# rifting_bronx_eden.net
KiCad netlist of a schematic drawn in EAGLE
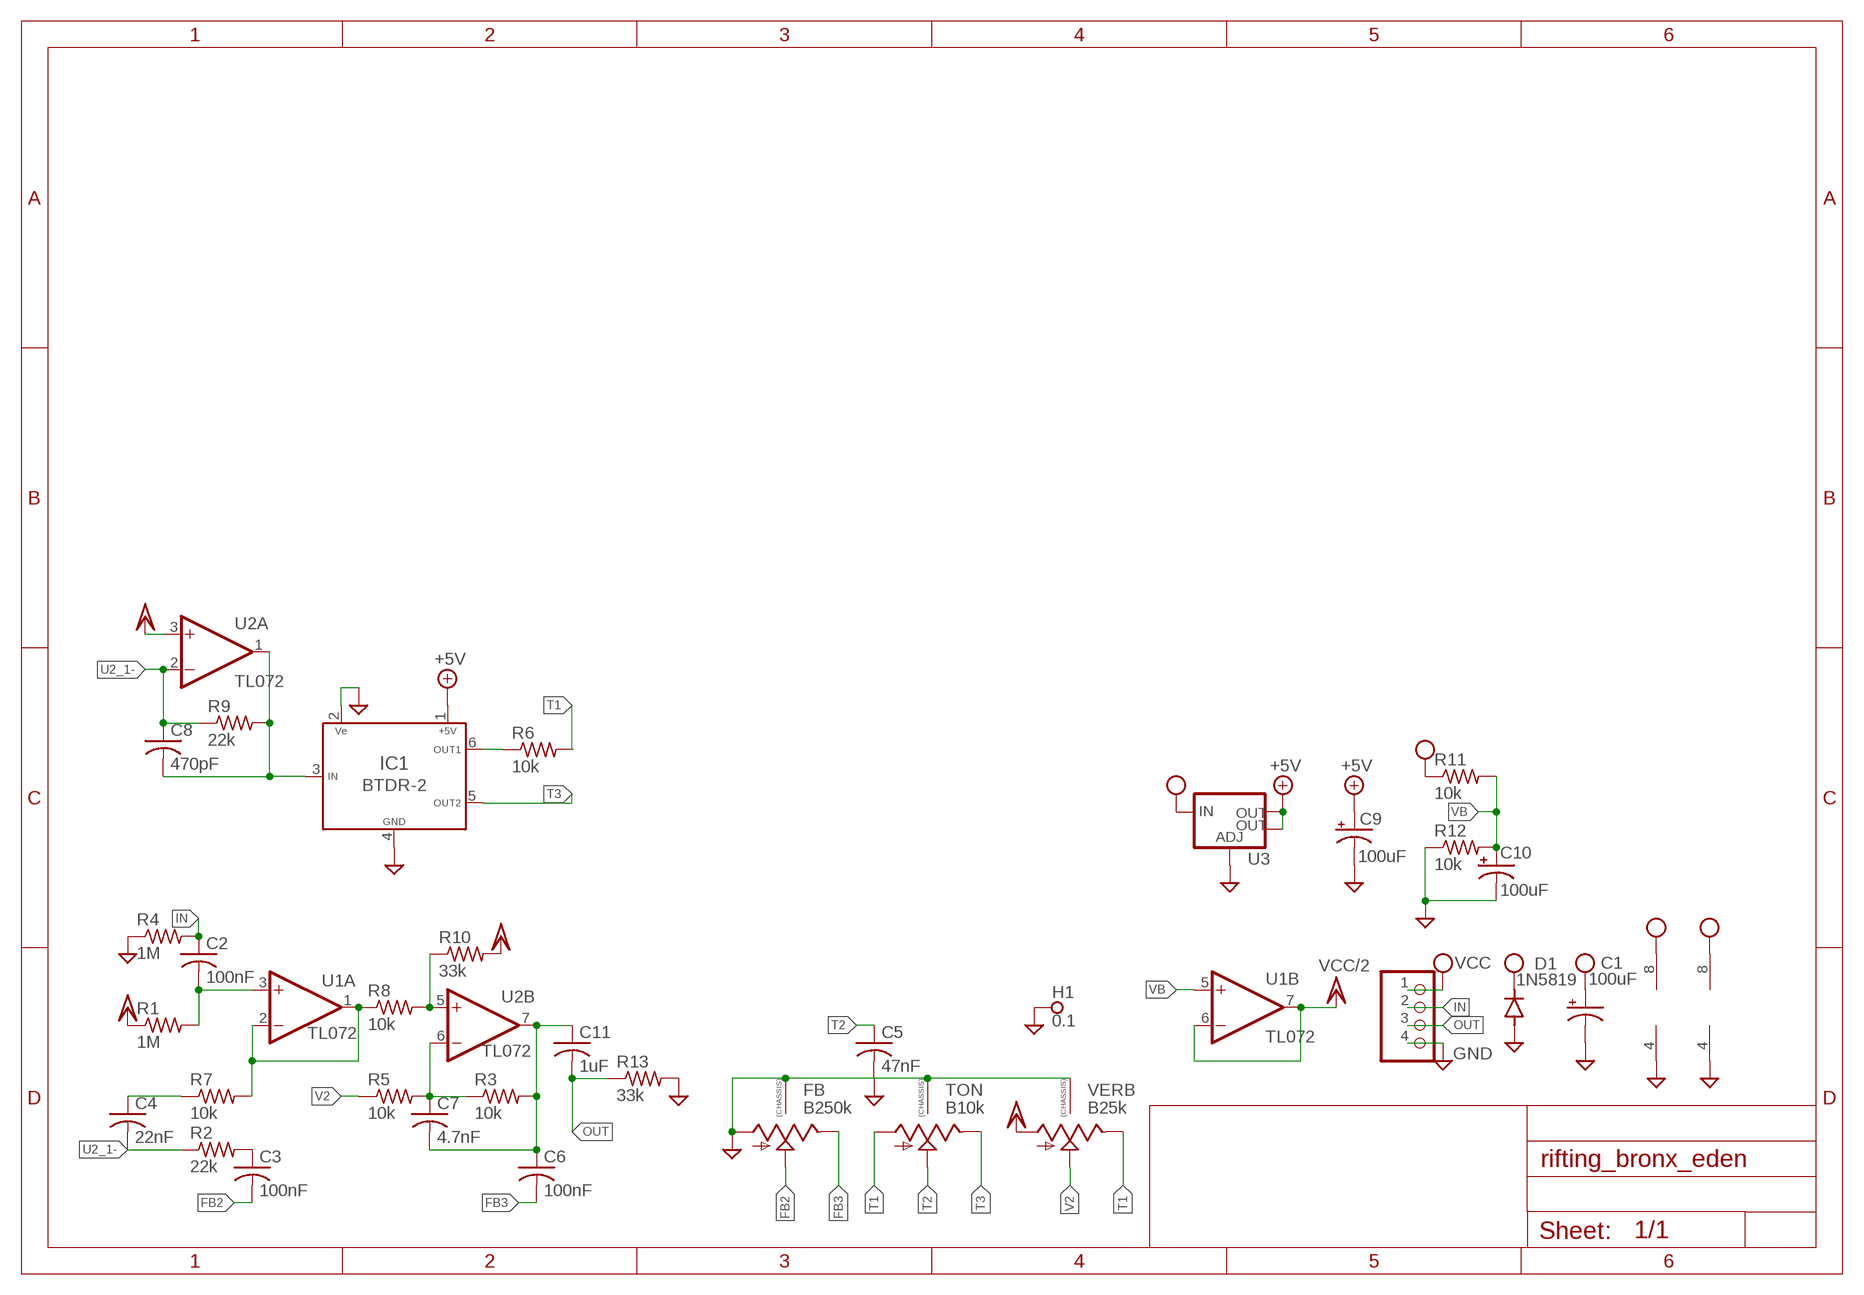
[diagram p0: schematic, sheet 1]

(export (version "E")
  (design (tool "Eeschema 10.0.6"))
  (components
    (comp (ref "C1")
      (value "100uF")
      (footprint "eagle-import:PAN_B_SMD+THRU")
      (libsource (lib "eagle-import") (part "CAP_SMD+THRUPAN_B"))
    )
    (comp (ref "C2")
      (value "100nF")
      (footprint "eagle-import:C0603")
      (libsource (lib "eagle-import") (part "C-USC0603"))
    )
    (comp (ref "C3")
      (value "100nF")
      (footprint "eagle-import:C0603")
      (libsource (lib "eagle-import") (part "C-USC0603"))
    )
    (comp (ref "C4")
      (value "22nF")
      (footprint "eagle-import:C0603")
      (libsource (lib "eagle-import") (part "C-USC0603"))
    )
    (comp (ref "C5")
      (value "47nF")
      (footprint "eagle-import:C0603")
      (libsource (lib "eagle-import") (part "C-USC0603"))
    )
    (comp (ref "C6")
      (value "100nF")
      (footprint "eagle-import:C0603")
      (libsource (lib "eagle-import") (part "C-USC0603"))
    )
    (comp (ref "C7")
      (value "4.7nF")
      (footprint "eagle-import:C0603")
      (libsource (lib "eagle-import") (part "C-USC0603"))
    )
    (comp (ref "C8")
      (value "470pF")
      (footprint "eagle-import:C0603")
      (libsource (lib "eagle-import") (part "C-USC0603"))
    )
    (comp (ref "C9")
      (value "100uF")
      (footprint "eagle-import:PAN_B_SMD+THRU")
      (libsource (lib "eagle-import") (part "CAP_SMD+THRUPAN_B"))
    )
    (comp (ref "C10")
      (value "100uF")
      (footprint "eagle-import:PAN_B_SMD+THRU")
      (libsource (lib "eagle-import") (part "CAP_SMD+THRUPAN_B"))
    )
    (comp (ref "C11")
      (value "1uF")
      (footprint "eagle-import:C0603")
      (libsource (lib "eagle-import") (part "C-USC0603"))
    )
    (comp (ref "D1")
      (value "1N5819")
      (footprint "eagle-import:SOD123")
      (libsource (lib "eagle-import") (part "DIODE-SOD123"))
    )
    (comp (ref "FB")
      (value "B250k")
      (footprint "eagle-import:9MM_SNAP-IN_POT")
      (libsource (lib "eagle-import") (part "9MM_SNAP-IN_POT_CHASSIS"))
    )
    (comp (ref "H1")
      (value "0.1")
      (footprint "eagle-import:PAD_0.1000")
      (libsource (lib "eagle-import") (part "SPECIAL_DRILL_0.1000"))
    )
    (comp (ref "IC1")
      (value "BTDR-2")
      (footprint "eagle-import:BTDR-2")
      (libsource (lib "eagle-import") (part "BTDR-2"))
    )
    (comp (ref "JP1")
      (value "PINHD-1X4")
      (footprint "eagle-import:1X04")
      (libsource (lib "eagle-import") (part "PINHD-1X4"))
    )
    (comp (ref "R1")
      (value "1M")
      (footprint "eagle-import:R0603")
      (libsource (lib "eagle-import") (part "R-US_R0603"))
    )
    (comp (ref "R2")
      (value "22k")
      (footprint "eagle-import:R0603")
      (libsource (lib "eagle-import") (part "R-US_R0603"))
    )
    (comp (ref "R3")
      (value "10k")
      (footprint "eagle-import:R0603")
      (libsource (lib "eagle-import") (part "R-US_R0603"))
    )
    (comp (ref "R4")
      (value "1M")
      (footprint "eagle-import:R0603")
      (libsource (lib "eagle-import") (part "R-US_R0603"))
    )
    (comp (ref "R5")
      (value "10k")
      (footprint "eagle-import:R0603")
      (libsource (lib "eagle-import") (part "R-US_R0603"))
    )
    (comp (ref "R6")
      (value "10k")
      (footprint "eagle-import:R0603")
      (libsource (lib "eagle-import") (part "R-US_R0603"))
    )
    (comp (ref "R7")
      (value "10k")
      (footprint "eagle-import:R0603")
      (libsource (lib "eagle-import") (part "R-US_R0603"))
    )
    (comp (ref "R8")
      (value "10k")
      (footprint "eagle-import:R0603")
      (libsource (lib "eagle-import") (part "R-US_R0603"))
    )
    (comp (ref "R9")
      (value "22k")
      (footprint "eagle-import:R0603")
      (libsource (lib "eagle-import") (part "R-US_R0603"))
    )
    (comp (ref "R10")
      (value "33k")
      (footprint "eagle-import:R0603")
      (libsource (lib "eagle-import") (part "R-US_R0603"))
    )
    (comp (ref "R11")
      (value "10k")
      (footprint "eagle-import:R0603")
      (libsource (lib "eagle-import") (part "R-US_R0603"))
    )
    (comp (ref "R12")
      (value "10k")
      (footprint "eagle-import:R0603")
      (libsource (lib "eagle-import") (part "R-US_R0603"))
    )
    (comp (ref "R13")
      (value "33k")
      (footprint "eagle-import:R0603")
      (libsource (lib "eagle-import") (part "R-US_R0603"))
    )
    (comp (ref "TON")
      (value "B10k")
      (footprint "eagle-import:9MM_SNAP-IN_POT")
      (libsource (lib "eagle-import") (part "9MM_SNAP-IN_POT_CHASSIS"))
    )
    (comp (ref "U1")
      (value "TL072")
      (footprint "eagle-import:TSSOP-8")
      (libsource (lib "eagle-import") (part "TL072TSSOP"))
    )
    (comp (ref "U2")
      (value "TL072")
      (footprint "eagle-import:TSSOP-8")
      (libsource (lib "eagle-import") (part "TL072TSSOP"))
    )
    (comp (ref "U3")
      (value "V_REG_LM1117SOT223")
      (footprint "eagle-import:SOT223")
      (libsource (lib "eagle-import") (part "V_REG_LM1117SOT223"))
    )
    (comp (ref "VERB")
      (value "B25k")
      (footprint "eagle-import:9MM_SNAP-IN_POT")
      (libsource (lib "eagle-import") (part "9MM_SNAP-IN_POT_CHASSIS"))
    )
  )
  (nets
    (net (code "1") (name "+5V") (class "Default")
      (node (ref "C9") (pin "+") (pinfunction "+_+") (pintype "passive"))
      (node (ref "C9") (pin "++") (pinfunction "+_++") (pintype "passive"))
      (node (ref "IC1") (pin "1") (pinfunction "1_1") (pintype "bidirectional"))
      (node (ref "U3") (pin "2") (pinfunction "OUT_2") (pintype "output"))
      (node (ref "U3") (pin "4") (pinfunction "OUT_4") (pintype "output"))
    )
    (net (code "2") (name "FB2") (class "Default")
      (node (ref "C3") (pin "2") (pinfunction "2_2") (pintype "passive"))
      (node (ref "FB") (pin "2") (pinfunction "S_2") (pintype "passive"))
    )
    (net (code "3") (name "FB3") (class "Default")
      (node (ref "C6") (pin "2") (pinfunction "2_2") (pintype "passive"))
      (node (ref "FB") (pin "3") (pinfunction "E_3") (pintype "passive"))
    )
    (net (code "4") (name "GND") (class "Default")
      (node (ref "C1") (pin "-") (pinfunction "-_-") (pintype "passive"))
      (node (ref "C1") (pin "--") (pinfunction "-_--") (pintype "passive"))
      (node (ref "C10") (pin "-") (pinfunction "-_-") (pintype "passive"))
      (node (ref "C10") (pin "--") (pinfunction "-_--") (pintype "passive"))
      (node (ref "C5") (pin "2") (pinfunction "2_2") (pintype "passive"))
      (node (ref "C9") (pin "-") (pinfunction "-_-") (pintype "passive"))
      (node (ref "C9") (pin "--") (pinfunction "-_--") (pintype "passive"))
      (node (ref "D1") (pin "A") (pinfunction "A_A") (pintype "passive"))
      (node (ref "FB") (pin "1") (pinfunction "A_1") (pintype "passive"))
      (node (ref "FB") (pin "CHASSIS1") (pinfunction "P$1_CHASSIS1") (pintype "passive"))
      (node (ref "FB") (pin "CHASSIS2") (pinfunction "P$1_CHASSIS2") (pintype "passive"))
      (node (ref "H1") (pin "1") (pinfunction "1_1") (pintype "passive"))
      (node (ref "IC1") (pin "2") (pinfunction "2_2") (pintype "bidirectional"))
      (node (ref "IC1") (pin "4") (pinfunction "4_4") (pintype "bidirectional"))
      (node (ref "JP1") (pin "4") (pinfunction "4_4") (pintype "passive"))
      (node (ref "R12") (pin "1") (pinfunction "1_1") (pintype "passive"))
      (node (ref "R13") (pin "2") (pinfunction "2_2") (pintype "passive"))
      (node (ref "R4") (pin "1") (pinfunction "1_1") (pintype "passive"))
      (node (ref "TON") (pin "CHASSIS1") (pinfunction "P$1_CHASSIS1") (pintype "passive"))
      (node (ref "TON") (pin "CHASSIS2") (pinfunction "P$1_CHASSIS2") (pintype "passive"))
      (node (ref "U1") (pin "4") (pinfunction "V-_4") (pintype "power_in"))
      (node (ref "U2") (pin "4") (pinfunction "V-_4") (pintype "power_in"))
      (node (ref "U3") (pin "1") (pinfunction "ADJ_1") (pintype "input"))
      (node (ref "VERB") (pin "CHASSIS1") (pinfunction "P$1_CHASSIS1") (pintype "passive"))
      (node (ref "VERB") (pin "CHASSIS2") (pinfunction "P$1_CHASSIS2") (pintype "passive"))
    )
    (net (code "5") (name "IN") (class "Default")
      (node (ref "C2") (pin "1") (pinfunction "1_1") (pintype "passive"))
      (node (ref "JP1") (pin "2") (pinfunction "2_2") (pintype "passive"))
      (node (ref "R4") (pin "2") (pinfunction "2_2") (pintype "passive"))
    )
    (net (code "6") (name "Net-(C3-Pad1)") (class "Default")
      (node (ref "C3") (pin "1") (pinfunction "1_1") (pintype "passive"))
      (node (ref "R2") (pin "2") (pinfunction "2_2") (pintype "passive"))
    )
    (net (code "7") (name "Net-(C4-Pad1)") (class "Default")
      (node (ref "C4") (pin "1") (pinfunction "1_1") (pintype "passive"))
      (node (ref "R7") (pin "1") (pinfunction "1_1") (pintype "passive"))
    )
    (net (code "8") (name "Net-(IC1-Pad6)") (class "Default")
      (node (ref "IC1") (pin "6") (pinfunction "6_6") (pintype "bidirectional"))
      (node (ref "R6") (pin "1") (pinfunction "1_1") (pintype "passive"))
    )
    (net (code "9") (name "Net-(U1A-+IN)") (class "Default")
      (node (ref "C2") (pin "2") (pinfunction "2_2") (pintype "passive"))
      (node (ref "R1") (pin "2") (pinfunction "2_2") (pintype "passive"))
      (node (ref "U1") (pin "3") (pinfunction "+IN_3") (pintype "input"))
    )
    (net (code "10") (name "Net-(U1A--IN)") (class "Default")
      (node (ref "R7") (pin "2") (pinfunction "2_2") (pintype "passive"))
      (node (ref "R8") (pin "1") (pinfunction "1_1") (pintype "passive"))
      (node (ref "U1") (pin "1") (pinfunction "OUT_1") (pintype "output"))
      (node (ref "U1") (pin "2") (pinfunction "-IN_2") (pintype "input"))
    )
    (net (code "11") (name "Net-(U2A-OUT)") (class "Default")
      (node (ref "C8") (pin "2") (pinfunction "2_2") (pintype "passive"))
      (node (ref "IC1") (pin "3") (pinfunction "3_3") (pintype "bidirectional"))
      (node (ref "R9") (pin "2") (pinfunction "2_2") (pintype "passive"))
      (node (ref "U2") (pin "1") (pinfunction "OUT_1") (pintype "output"))
    )
    (net (code "12") (name "Net-(U2B-+IN)") (class "Default")
      (node (ref "R10") (pin "1") (pinfunction "1_1") (pintype "passive"))
      (node (ref "R8") (pin "2") (pinfunction "2_2") (pintype "passive"))
      (node (ref "U2") (pin "5") (pinfunction "+IN_5") (pintype "input"))
    )
    (net (code "13") (name "Net-(U2B--IN)") (class "Default")
      (node (ref "C7") (pin "1") (pinfunction "1_1") (pintype "passive"))
      (node (ref "R3") (pin "1") (pinfunction "1_1") (pintype "passive"))
      (node (ref "R5") (pin "2") (pinfunction "2_2") (pintype "passive"))
      (node (ref "U2") (pin "6") (pinfunction "-IN_6") (pintype "input"))
    )
    (net (code "14") (name "Net-(U2B-OUT)") (class "Default")
      (node (ref "C11") (pin "1") (pinfunction "1_1") (pintype "passive"))
      (node (ref "C6") (pin "1") (pinfunction "1_1") (pintype "passive"))
      (node (ref "C7") (pin "2") (pinfunction "2_2") (pintype "passive"))
      (node (ref "R3") (pin "2") (pinfunction "2_2") (pintype "passive"))
      (node (ref "U2") (pin "7") (pinfunction "OUT_7") (pintype "output"))
    )
    (net (code "15") (name "OUT") (class "Default")
      (node (ref "C11") (pin "2") (pinfunction "2_2") (pintype "passive"))
      (node (ref "JP1") (pin "3") (pinfunction "3_3") (pintype "passive"))
      (node (ref "R13") (pin "1") (pinfunction "1_1") (pintype "passive"))
    )
    (net (code "16") (name "T1") (class "Default")
      (node (ref "R6") (pin "2") (pinfunction "2_2") (pintype "passive"))
      (node (ref "TON") (pin "1") (pinfunction "A_1") (pintype "passive"))
      (node (ref "VERB") (pin "3") (pinfunction "E_3") (pintype "passive"))
    )
    (net (code "17") (name "T2") (class "Default")
      (node (ref "C5") (pin "1") (pinfunction "1_1") (pintype "passive"))
      (node (ref "TON") (pin "2") (pinfunction "S_2") (pintype "passive"))
    )
    (net (code "18") (name "T3") (class "Default")
      (node (ref "IC1") (pin "5") (pinfunction "5_5") (pintype "bidirectional"))
      (node (ref "TON") (pin "3") (pinfunction "E_3") (pintype "passive"))
    )
    (net (code "19") (name "U2_1-") (class "Default")
      (node (ref "C4") (pin "2") (pinfunction "2_2") (pintype "passive"))
      (node (ref "C8") (pin "1") (pinfunction "1_1") (pintype "passive"))
      (node (ref "R2") (pin "1") (pinfunction "1_1") (pintype "passive"))
      (node (ref "R9") (pin "1") (pinfunction "1_1") (pintype "passive"))
      (node (ref "U2") (pin "2") (pinfunction "-IN_2") (pintype "input"))
    )
    (net (code "20") (name "V2") (class "Default")
      (node (ref "R5") (pin "1") (pinfunction "1_1") (pintype "passive"))
      (node (ref "VERB") (pin "2") (pinfunction "S_2") (pintype "passive"))
    )
    (net (code "21") (name "VB") (class "Default")
      (node (ref "C10") (pin "+") (pinfunction "+_+") (pintype "passive"))
      (node (ref "C10") (pin "++") (pinfunction "+_++") (pintype "passive"))
      (node (ref "R11") (pin "2") (pinfunction "2_2") (pintype "passive"))
      (node (ref "R12") (pin "2") (pinfunction "2_2") (pintype "passive"))
      (node (ref "U1") (pin "5") (pinfunction "+IN_5") (pintype "input"))
    )
    (net (code "22") (name "VCC") (class "Default")
      (node (ref "C1") (pin "+") (pinfunction "+_+") (pintype "passive"))
      (node (ref "C1") (pin "++") (pinfunction "+_++") (pintype "passive"))
      (node (ref "D1") (pin "C") (pinfunction "C_C") (pintype "passive"))
      (node (ref "JP1") (pin "1") (pinfunction "1_1") (pintype "passive"))
      (node (ref "R11") (pin "1") (pinfunction "1_1") (pintype "passive"))
      (node (ref "U1") (pin "8") (pinfunction "V+_8") (pintype "power_in"))
      (node (ref "U2") (pin "8") (pinfunction "V+_8") (pintype "power_in"))
      (node (ref "U3") (pin "3") (pinfunction "IN_3") (pintype "input"))
    )
    (net (code "23") (name "VCC{slash}2") (class "Default")
      (node (ref "R1") (pin "1") (pinfunction "1_1") (pintype "passive"))
      (node (ref "R10") (pin "2") (pinfunction "2_2") (pintype "passive"))
      (node (ref "U1") (pin "6") (pinfunction "-IN_6") (pintype "input"))
      (node (ref "U1") (pin "7") (pinfunction "OUT_7") (pintype "output"))
      (node (ref "U2") (pin "3") (pinfunction "+IN_3") (pintype "input"))
      (node (ref "VERB") (pin "1") (pinfunction "A_1") (pintype "passive"))
    )
  )
)
